# CiroSonda_V2.net
KiCad netlist of a schematic drawn in EAGLE
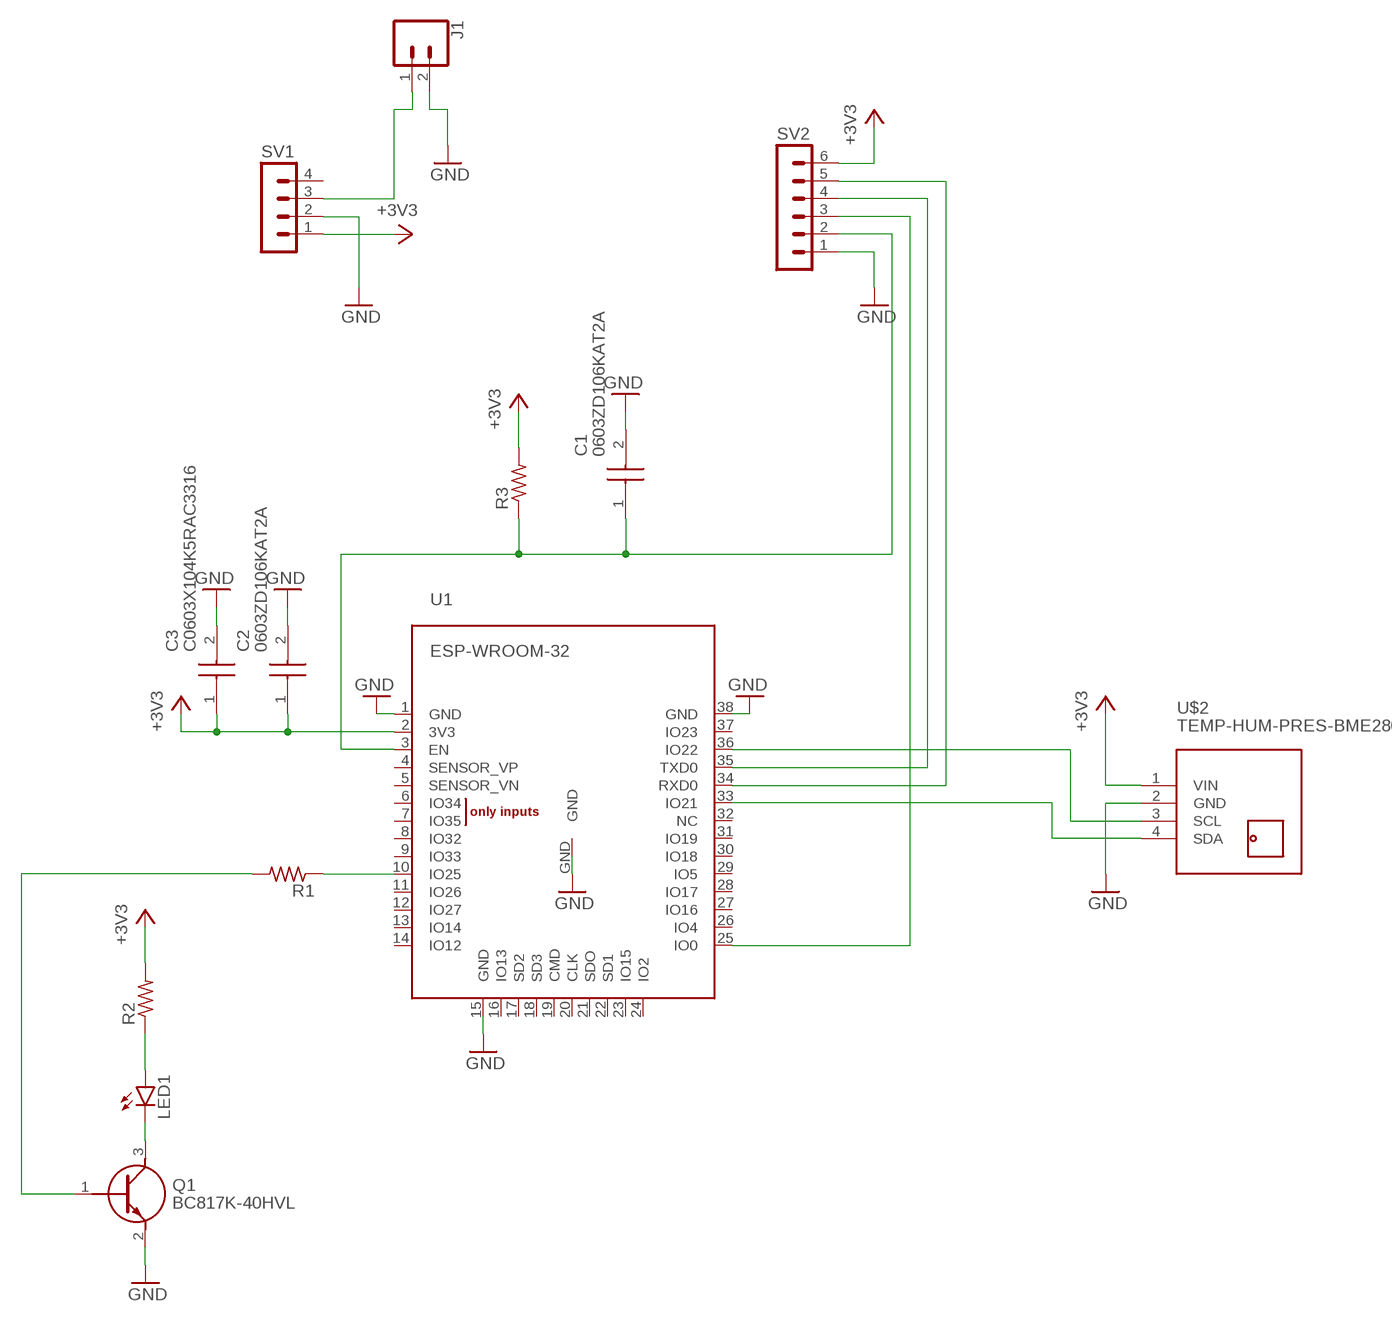
[diagram p0: schematic, sheet 1]

(export (version "E")
  (design (tool "Eeschema 10.0.6"))
  (components
    (comp (ref "C1")
      (value "0603ZD106KAT2A")
      (footprint "eagle-import:CAPC1608X90N")
      (fields (field (name "MOUSER_PART_NUMBER") "581-0603ZD106KAT2A"))
      (libsource (lib "eagle-import") (part "0603ZD106KAT2A"))
    )
    (comp (ref "C2")
      (value "0603ZD106KAT2A")
      (footprint "eagle-import:CAPC1608X90N")
      (fields (field (name "MOUSER_PART_NUMBER") "581-0603ZD106KAT2A"))
      (libsource (lib "eagle-import") (part "0603ZD106KAT2A"))
    )
    (comp (ref "C3")
      (value "C0603X104K5RAC3316")
      (footprint "eagle-import:CAPC1608X95N")
      (fields (field (name "MOUSER_PART_NUMBER") "80-C0603X104K5R3316"))
      (libsource (lib "eagle-import") (part "C0603X104K5RAC3316"))
    )
    (comp (ref "J1")
      (value "CONN_025MM")
      (footprint "eagle-import:SCREWTERMINAL-5MM-2")
      (libsource (lib "eagle-import") (part "CONN_025MM"))
    )
    (comp (ref "LED1")
      (value "LED5MM")
      (footprint "eagle-import:LED5MM")
      (libsource (lib "eagle-import") (part "LED5MM"))
    )
    (comp (ref "Q1")
      (value "BC817K-40HVL")
      (footprint "eagle-import:SOT95P230X110-3N")
      (fields (field (name "MOUSER_PART_NUMBER") "771-BC817K-40HVL"))
      (libsource (lib "eagle-import") (part "BC817K-40HVL"))
    )
    (comp (ref "R1")
      (value "R-US_R0603")
      (footprint "eagle-import:R0603")
      (libsource (lib "eagle-import") (part "R-US_R0603"))
    )
    (comp (ref "R2")
      (value "R-US_R0805")
      (footprint "eagle-import:R0805")
      (libsource (lib "eagle-import") (part "R-US_R0805"))
    )
    (comp (ref "R3")
      (value "R-US_R0603")
      (footprint "eagle-import:R0603")
      (libsource (lib "eagle-import") (part "R-US_R0603"))
    )
    (comp (ref "SV1")
      (value "MA04-1")
      (footprint "eagle-import:MA04-1")
      (libsource (lib "eagle-import") (part "MA04-1"))
    )
    (comp (ref "SV2")
      (value "MA06-1")
      (footprint "eagle-import:MA06-1")
      (libsource (lib "eagle-import") (part "MA06-1"))
    )
    (comp (ref "U$2")
      (value "TEMP-HUM-PRES-BME280")
      (footprint "eagle-import:TEMP-HUM-PRES-BME280")
      (libsource (lib "eagle-import") (part "TEMP-HUM-PRES-BME280"))
    )
    (comp (ref "U1")
      (value "ESP-WROOM-32")
      (footprint "eagle-import:ESP-WROOM-32")
      (libsource (lib "eagle-import") (part "ESP-WROOM-32"))
    )
  )
  (nets
    (net (code "1") (name "+3V3") (class "Default")
      (node (ref "C2") (pin "1") (pinfunction "1_1") (pintype "bidirectional"))
      (node (ref "C3") (pin "1") (pinfunction "1_1") (pintype "bidirectional"))
      (node (ref "R2") (pin "2") (pinfunction "2_2") (pintype "passive"))
      (node (ref "R3") (pin "2") (pinfunction "2_2") (pintype "passive"))
      (node (ref "SV1") (pin "1") (pinfunction "1_1") (pintype "passive"))
      (node (ref "SV2") (pin "6") (pinfunction "6_6") (pintype "passive"))
      (node (ref "U$2") (pin "1") (pinfunction "VIN_1") (pintype "power_in"))
      (node (ref "U1") (pin "2") (pinfunction "3V3_2") (pintype "bidirectional"))
    )
    (net (code "2") (name "GND") (class "Default")
      (node (ref "C1") (pin "2") (pinfunction "2_2") (pintype "bidirectional"))
      (node (ref "C2") (pin "2") (pinfunction "2_2") (pintype "bidirectional"))
      (node (ref "C3") (pin "2") (pinfunction "2_2") (pintype "bidirectional"))
      (node (ref "J1") (pin "2") (pinfunction "2_2") (pintype "passive"))
      (node (ref "Q1") (pin "2") (pinfunction "E_2") (pintype "bidirectional"))
      (node (ref "SV1") (pin "2") (pinfunction "2_2") (pintype "passive"))
      (node (ref "SV2") (pin "1") (pinfunction "1_1") (pintype "passive"))
      (node (ref "U$2") (pin "2") (pinfunction "GND_2") (pintype "power_in"))
      (node (ref "U1") (pin "1") (pinfunction "GND_1") (pintype "bidirectional"))
      (node (ref "U1") (pin "15") (pinfunction "GND_15") (pintype "bidirectional"))
      (node (ref "U1") (pin "38") (pinfunction "GND_38") (pintype "bidirectional"))
      (node (ref "U1") (pin "GND") (pinfunction "GND_GND") (pintype "bidirectional"))
    )
    (net (code "3") (name "Net-(J1-Pad1)") (class "Default")
      (node (ref "J1") (pin "1") (pinfunction "1_1") (pintype "passive"))
      (node (ref "SV1") (pin "3") (pinfunction "3_3") (pintype "passive"))
    )
    (net (code "4") (name "Net-(LED1-C)") (class "Default")
      (node (ref "LED1") (pin "K") (pinfunction "C_K") (pintype "passive"))
      (node (ref "Q1") (pin "3") (pinfunction "C_3") (pintype "bidirectional"))
    )
    (net (code "5") (name "Net-(LED1-PadA)") (class "Default")
      (node (ref "LED1") (pin "A") (pinfunction "A_A") (pintype "passive"))
      (node (ref "R2") (pin "1") (pinfunction "1_1") (pintype "passive"))
    )
    (net (code "6") (name "Net-(Q1-B)") (class "Default")
      (node (ref "Q1") (pin "1") (pinfunction "B_1") (pintype "bidirectional"))
      (node (ref "R1") (pin "2") (pinfunction "2_2") (pintype "passive"))
    )
    (net (code "7") (name "Net-(U$2-SCL)") (class "Default")
      (node (ref "U$2") (pin "3") (pinfunction "SCL_3") (pintype "bidirectional"))
      (node (ref "U1") (pin "36") (pinfunction "IO22_36") (pintype "bidirectional"))
    )
    (net (code "8") (name "Net-(U$2-SDA)") (class "Default")
      (node (ref "U$2") (pin "4") (pinfunction "SDA_4") (pintype "bidirectional"))
      (node (ref "U1") (pin "33") (pinfunction "IO21_33") (pintype "bidirectional"))
    )
    (net (code "9") (name "Net-(U1-EN)") (class "Default")
      (node (ref "C1") (pin "1") (pinfunction "1_1") (pintype "bidirectional"))
      (node (ref "R3") (pin "1") (pinfunction "1_1") (pintype "passive"))
      (node (ref "SV2") (pin "2") (pinfunction "2_2") (pintype "passive"))
      (node (ref "U1") (pin "3") (pinfunction "EN_3") (pintype "bidirectional"))
    )
    (net (code "10") (name "Net-(U1-IO0)") (class "Default")
      (node (ref "SV2") (pin "3") (pinfunction "3_3") (pintype "passive"))
      (node (ref "U1") (pin "25") (pinfunction "IO0_25") (pintype "bidirectional"))
    )
    (net (code "11") (name "Net-(U1-IO25)") (class "Default")
      (node (ref "R1") (pin "1") (pinfunction "1_1") (pintype "passive"))
      (node (ref "U1") (pin "10") (pinfunction "IO25_10") (pintype "bidirectional"))
    )
    (net (code "12") (name "Net-(U1-RXD0)") (class "Default")
      (node (ref "SV2") (pin "5") (pinfunction "5_5") (pintype "passive"))
      (node (ref "U1") (pin "34") (pinfunction "RXD0_34") (pintype "bidirectional"))
    )
    (net (code "13") (name "Net-(U1-TXD0)") (class "Default")
      (node (ref "SV2") (pin "4") (pinfunction "4_4") (pintype "passive"))
      (node (ref "U1") (pin "35") (pinfunction "TXD0_35") (pintype "bidirectional"))
    )
    (net (code "14") (name "unconnected-(SV1-Pad4)") (class "Default")
      (node (ref "SV1") (pin "4") (pinfunction "4_4") (pintype "passive"))
    )
    (net (code "15") (name "unconnected-(U1-CLK-Pad20)") (class "Default")
      (node (ref "U1") (pin "20") (pinfunction "CLK_20") (pintype "bidirectional"))
    )
    (net (code "16") (name "unconnected-(U1-CMD-Pad19)") (class "Default")
      (node (ref "U1") (pin "19") (pinfunction "CMD_19") (pintype "bidirectional"))
    )
    (net (code "17") (name "unconnected-(U1-IO2-Pad24)") (class "Default")
      (node (ref "U1") (pin "24") (pinfunction "IO2_24") (pintype "bidirectional"))
    )
    (net (code "18") (name "unconnected-(U1-IO4-Pad26)") (class "Default")
      (node (ref "U1") (pin "26") (pinfunction "IO4_26") (pintype "bidirectional"))
    )
    (net (code "19") (name "unconnected-(U1-IO5-Pad29)") (class "Default")
      (node (ref "U1") (pin "29") (pinfunction "IO5_29") (pintype "bidirectional"))
    )
    (net (code "20") (name "unconnected-(U1-IO12-Pad14)") (class "Default")
      (node (ref "U1") (pin "14") (pinfunction "IO12_14") (pintype "bidirectional"))
    )
    (net (code "21") (name "unconnected-(U1-IO13-Pad16)") (class "Default")
      (node (ref "U1") (pin "16") (pinfunction "IO13_16") (pintype "bidirectional"))
    )
    (net (code "22") (name "unconnected-(U1-IO14-Pad13)") (class "Default")
      (node (ref "U1") (pin "13") (pinfunction "IO14_13") (pintype "bidirectional"))
    )
    (net (code "23") (name "unconnected-(U1-IO15-Pad23)") (class "Default")
      (node (ref "U1") (pin "23") (pinfunction "IO15_23") (pintype "bidirectional"))
    )
    (net (code "24") (name "unconnected-(U1-IO16-Pad27)") (class "Default")
      (node (ref "U1") (pin "27") (pinfunction "IO16_27") (pintype "bidirectional"))
    )
    (net (code "25") (name "unconnected-(U1-IO17-Pad28)") (class "Default")
      (node (ref "U1") (pin "28") (pinfunction "IO17_28") (pintype "bidirectional"))
    )
    (net (code "26") (name "unconnected-(U1-IO18-Pad30)") (class "Default")
      (node (ref "U1") (pin "30") (pinfunction "IO18_30") (pintype "bidirectional"))
    )
    (net (code "27") (name "unconnected-(U1-IO19-Pad31)") (class "Default")
      (node (ref "U1") (pin "31") (pinfunction "IO19_31") (pintype "bidirectional"))
    )
    (net (code "28") (name "unconnected-(U1-IO23-Pad37)") (class "Default")
      (node (ref "U1") (pin "37") (pinfunction "IO23_37") (pintype "bidirectional"))
    )
    (net (code "29") (name "unconnected-(U1-IO26-Pad11)") (class "Default")
      (node (ref "U1") (pin "11") (pinfunction "IO26_11") (pintype "bidirectional"))
    )
    (net (code "30") (name "unconnected-(U1-IO27-Pad12)") (class "Default")
      (node (ref "U1") (pin "12") (pinfunction "IO27_12") (pintype "bidirectional"))
    )
    (net (code "31") (name "unconnected-(U1-IO32-Pad8)") (class "Default")
      (node (ref "U1") (pin "8") (pinfunction "IO32_8") (pintype "bidirectional"))
    )
    (net (code "32") (name "unconnected-(U1-IO33-Pad9)") (class "Default")
      (node (ref "U1") (pin "9") (pinfunction "IO33_9") (pintype "bidirectional"))
    )
    (net (code "33") (name "unconnected-(U1-IO34-Pad6)") (class "Default")
      (node (ref "U1") (pin "6") (pinfunction "IO34_6") (pintype "input"))
    )
    (net (code "34") (name "unconnected-(U1-IO35-Pad7)") (class "Default")
      (node (ref "U1") (pin "7") (pinfunction "IO35_7") (pintype "input"))
    )
    (net (code "35") (name "unconnected-(U1-NC-Pad32)") (class "Default")
      (node (ref "U1") (pin "32") (pinfunction "NC_32") (pintype "bidirectional"))
    )
    (net (code "36") (name "unconnected-(U1-SD1-Pad22)") (class "Default")
      (node (ref "U1") (pin "22") (pinfunction "SD1_22") (pintype "bidirectional"))
    )
    (net (code "37") (name "unconnected-(U1-SD2-Pad17)") (class "Default")
      (node (ref "U1") (pin "17") (pinfunction "SD2_17") (pintype "bidirectional"))
    )
    (net (code "38") (name "unconnected-(U1-SD3-Pad18)") (class "Default")
      (node (ref "U1") (pin "18") (pinfunction "SD3_18") (pintype "bidirectional"))
    )
    (net (code "39") (name "unconnected-(U1-SDO-Pad21)") (class "Default")
      (node (ref "U1") (pin "21") (pinfunction "SDO_21") (pintype "bidirectional"))
    )
    (net (code "40") (name "unconnected-(U1-SENSOR_VN-Pad5)") (class "Default")
      (node (ref "U1") (pin "5") (pinfunction "SENSOR_VN_5") (pintype "input"))
    )
    (net (code "41") (name "unconnected-(U1-SENSOR_VP-Pad4)") (class "Default")
      (node (ref "U1") (pin "4") (pinfunction "SENSOR_VP_4") (pintype "input"))
    )
  )
)
